# flasher.net
KiCad netlist of a schematic drawn in EAGLE
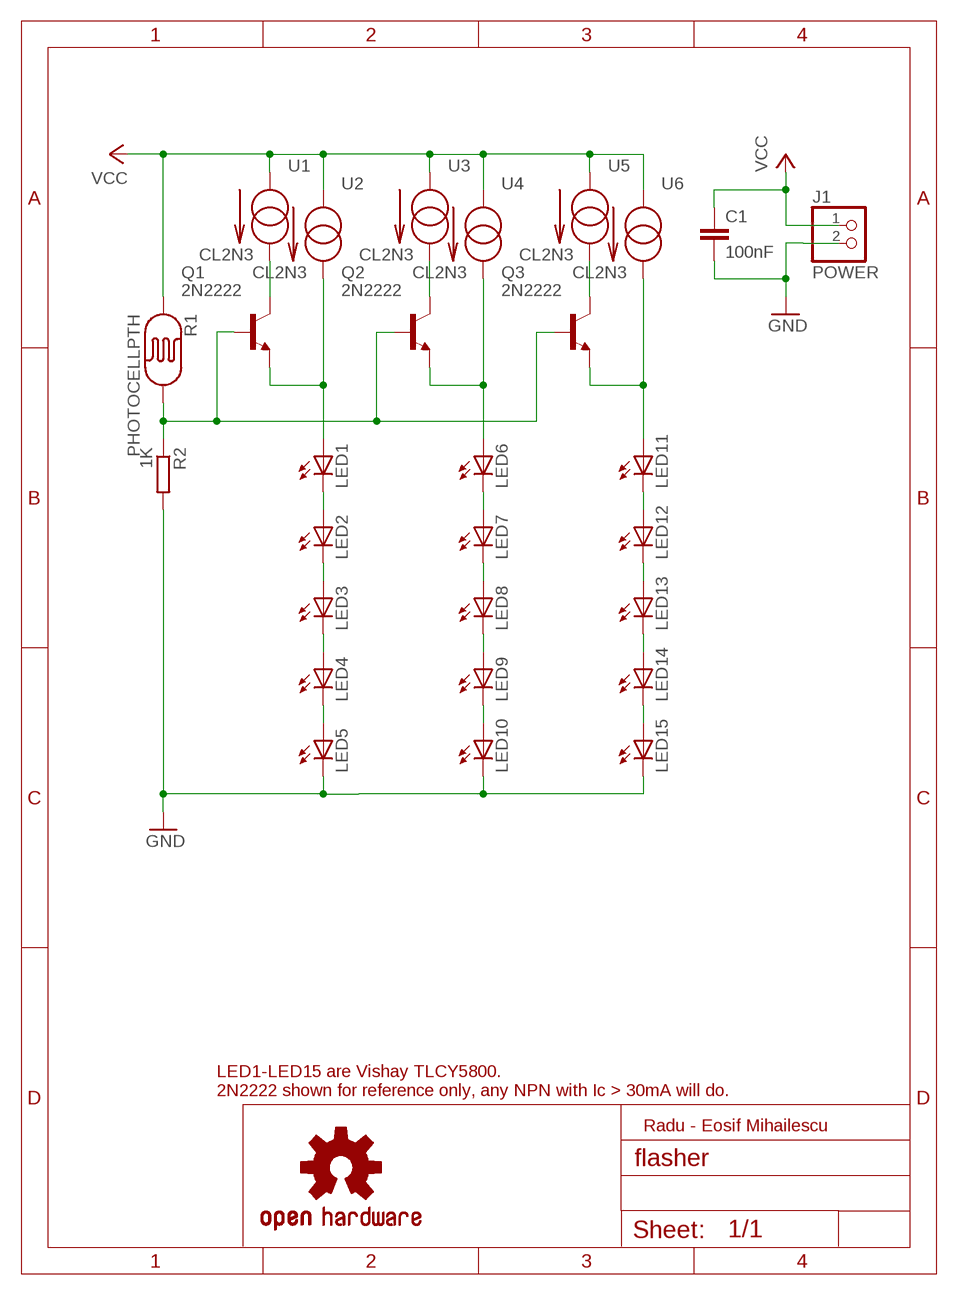
[diagram p0: schematic, sheet 1]

(export (version "E")
  (design (tool "Eeschema 10.0.6"))
  (components
    (comp (ref "C1")
      (value "100nF")
      (footprint "eagle-import:C050-025X075")
      (libsource (lib "eagle-import") (part "C-EU050-025X075"))
    )
    (comp (ref "J1")
      (value "POWER")
      (footprint "eagle-import:1X02_90")
      (libsource (lib "eagle-import") (part "PINHD-1X2/90"))
    )
    (comp (ref "LED1")
      (value "LED5MM")
      (footprint "eagle-import:LED5MM")
      (libsource (lib "eagle-import") (part "LED5MM"))
    )
    (comp (ref "LED2")
      (value "LED5MM")
      (footprint "eagle-import:LED5MM")
      (libsource (lib "eagle-import") (part "LED5MM"))
    )
    (comp (ref "LED3")
      (value "LED5MM")
      (footprint "eagle-import:LED5MM")
      (libsource (lib "eagle-import") (part "LED5MM"))
    )
    (comp (ref "LED4")
      (value "LED5MM")
      (footprint "eagle-import:LED5MM")
      (libsource (lib "eagle-import") (part "LED5MM"))
    )
    (comp (ref "LED5")
      (value "LED5MM")
      (footprint "eagle-import:LED5MM")
      (libsource (lib "eagle-import") (part "LED5MM"))
    )
    (comp (ref "LED6")
      (value "LED5MM")
      (footprint "eagle-import:LED5MM")
      (libsource (lib "eagle-import") (part "LED5MM"))
    )
    (comp (ref "LED7")
      (value "LED5MM")
      (footprint "eagle-import:LED5MM")
      (libsource (lib "eagle-import") (part "LED5MM"))
    )
    (comp (ref "LED8")
      (value "LED5MM")
      (footprint "eagle-import:LED5MM")
      (libsource (lib "eagle-import") (part "LED5MM"))
    )
    (comp (ref "LED9")
      (value "LED5MM")
      (footprint "eagle-import:LED5MM")
      (libsource (lib "eagle-import") (part "LED5MM"))
    )
    (comp (ref "LED10")
      (value "LED5MM")
      (footprint "eagle-import:LED5MM")
      (libsource (lib "eagle-import") (part "LED5MM"))
    )
    (comp (ref "LED11")
      (value "LED5MM")
      (footprint "eagle-import:LED5MM")
      (libsource (lib "eagle-import") (part "LED5MM"))
    )
    (comp (ref "LED12")
      (value "LED5MM")
      (footprint "eagle-import:LED5MM")
      (libsource (lib "eagle-import") (part "LED5MM"))
    )
    (comp (ref "LED13")
      (value "LED5MM")
      (footprint "eagle-import:LED5MM")
      (libsource (lib "eagle-import") (part "LED5MM"))
    )
    (comp (ref "LED14")
      (value "LED5MM")
      (footprint "eagle-import:LED5MM")
      (libsource (lib "eagle-import") (part "LED5MM"))
    )
    (comp (ref "LED15")
      (value "LED5MM")
      (footprint "eagle-import:LED5MM")
      (libsource (lib "eagle-import") (part "LED5MM"))
    )
    (comp (ref "LOGO1")
      (value "OSHW-LOGOL")
      (footprint "eagle-import:OSHW-LOGO-L")
      (libsource (lib "eagle-import") (part "OSHW-LOGOL"))
    )
    (comp (ref "Q1")
      (value "2N2222")
      (footprint "eagle-import:TO92-EBC")
      (libsource (lib "eagle-import") (part "-NPN-TO92-EBC2N2222"))
    )
    (comp (ref "Q2")
      (value "2N2222")
      (footprint "eagle-import:TO92-EBC")
      (libsource (lib "eagle-import") (part "-NPN-TO92-EBC2N2222"))
    )
    (comp (ref "Q3")
      (value "2N2222")
      (footprint "eagle-import:TO92-EBC")
      (libsource (lib "eagle-import") (part "-NPN-TO92-EBC2N2222"))
    )
    (comp (ref "R1")
      (value "PHOTOCELLPTH")
      (footprint "eagle-import:PHOTOCELL")
      (libsource (lib "eagle-import") (part "PHOTOCELLPTH"))
    )
    (comp (ref "R2")
      (value "1K")
      (footprint "eagle-import:0204_7")
      (libsource (lib "eagle-import") (part "R-EU_0204/7"))
    )
    (comp (ref "U1")
      (value "CL2N3")
      (footprint "eagle-import:TO-92")
      (libsource (lib "eagle-import") (part "CL2N3"))
    )
    (comp (ref "U2")
      (value "CL2N3")
      (footprint "eagle-import:TO-92")
      (libsource (lib "eagle-import") (part "CL2N3"))
    )
    (comp (ref "U3")
      (value "CL2N3")
      (footprint "eagle-import:TO-92")
      (libsource (lib "eagle-import") (part "CL2N3"))
    )
    (comp (ref "U4")
      (value "CL2N3")
      (footprint "eagle-import:TO-92")
      (libsource (lib "eagle-import") (part "CL2N3"))
    )
    (comp (ref "U5")
      (value "CL2N3")
      (footprint "eagle-import:TO-92")
      (libsource (lib "eagle-import") (part "CL2N3"))
    )
    (comp (ref "U6")
      (value "CL2N3")
      (footprint "eagle-import:TO-92")
      (libsource (lib "eagle-import") (part "CL2N3"))
    )
  )
  (nets
    (net (code "1") (name "GND") (class "Default")
      (node (ref "C1") (pin "2") (pinfunction "2_2") (pintype "passive"))
      (node (ref "J1") (pin "2") (pinfunction "2_2") (pintype "passive"))
      (node (ref "LED10") (pin "K") (pinfunction "C_K") (pintype "passive"))
      (node (ref "LED15") (pin "K") (pinfunction "C_K") (pintype "passive"))
      (node (ref "LED5") (pin "K") (pinfunction "C_K") (pintype "passive"))
      (node (ref "R2") (pin "2") (pinfunction "2_2") (pintype "passive"))
    )
    (net (code "2") (name "Net-(LED1-C)") (class "Default")
      (node (ref "LED1") (pin "K") (pinfunction "C_K") (pintype "passive"))
      (node (ref "LED2") (pin "A") (pinfunction "A_A") (pintype "passive"))
    )
    (net (code "3") (name "Net-(LED2-C)") (class "Default")
      (node (ref "LED2") (pin "K") (pinfunction "C_K") (pintype "passive"))
      (node (ref "LED3") (pin "A") (pinfunction "A_A") (pintype "passive"))
    )
    (net (code "4") (name "Net-(LED3-C)") (class "Default")
      (node (ref "LED3") (pin "K") (pinfunction "C_K") (pintype "passive"))
      (node (ref "LED4") (pin "A") (pinfunction "A_A") (pintype "passive"))
    )
    (net (code "5") (name "Net-(LED4-C)") (class "Default")
      (node (ref "LED4") (pin "K") (pinfunction "C_K") (pintype "passive"))
      (node (ref "LED5") (pin "A") (pinfunction "A_A") (pintype "passive"))
    )
    (net (code "6") (name "Net-(LED6-C)") (class "Default")
      (node (ref "LED6") (pin "K") (pinfunction "C_K") (pintype "passive"))
      (node (ref "LED7") (pin "A") (pinfunction "A_A") (pintype "passive"))
    )
    (net (code "7") (name "Net-(LED7-C)") (class "Default")
      (node (ref "LED7") (pin "K") (pinfunction "C_K") (pintype "passive"))
      (node (ref "LED8") (pin "A") (pinfunction "A_A") (pintype "passive"))
    )
    (net (code "8") (name "Net-(LED8-C)") (class "Default")
      (node (ref "LED8") (pin "K") (pinfunction "C_K") (pintype "passive"))
      (node (ref "LED9") (pin "A") (pinfunction "A_A") (pintype "passive"))
    )
    (net (code "9") (name "Net-(LED9-C)") (class "Default")
      (node (ref "LED10") (pin "A") (pinfunction "A_A") (pintype "passive"))
      (node (ref "LED9") (pin "K") (pinfunction "C_K") (pintype "passive"))
    )
    (net (code "10") (name "Net-(LED11-C)") (class "Default")
      (node (ref "LED11") (pin "K") (pinfunction "C_K") (pintype "passive"))
      (node (ref "LED12") (pin "A") (pinfunction "A_A") (pintype "passive"))
    )
    (net (code "11") (name "Net-(LED12-C)") (class "Default")
      (node (ref "LED12") (pin "K") (pinfunction "C_K") (pintype "passive"))
      (node (ref "LED13") (pin "A") (pinfunction "A_A") (pintype "passive"))
    )
    (net (code "12") (name "Net-(LED13-C)") (class "Default")
      (node (ref "LED13") (pin "K") (pinfunction "C_K") (pintype "passive"))
      (node (ref "LED14") (pin "A") (pinfunction "A_A") (pintype "passive"))
    )
    (net (code "13") (name "Net-(LED14-C)") (class "Default")
      (node (ref "LED14") (pin "K") (pinfunction "C_K") (pintype "passive"))
      (node (ref "LED15") (pin "A") (pinfunction "A_A") (pintype "passive"))
    )
    (net (code "14") (name "Net-(R1-P$2)") (class "Default")
      (node (ref "Q1") (pin "B") (pinfunction "B_B") (pintype "passive"))
      (node (ref "Q2") (pin "B") (pinfunction "B_B") (pintype "passive"))
      (node (ref "Q3") (pin "B") (pinfunction "B_B") (pintype "passive"))
      (node (ref "R1") (pin "2") (pinfunction "P$2_2") (pintype "bidirectional"))
      (node (ref "R2") (pin "1") (pinfunction "1_1") (pintype "passive"))
    )
    (net (code "15") (name "Net-(U1-OUT)") (class "Default")
      (node (ref "Q1") (pin "C") (pinfunction "C_C") (pintype "passive"))
      (node (ref "U1") (pin "3") (pinfunction "OUT_3") (pintype "output"))
    )
    (net (code "16") (name "Net-(U2-OUT)") (class "Default")
      (node (ref "LED1") (pin "A") (pinfunction "A_A") (pintype "passive"))
      (node (ref "Q1") (pin "E") (pinfunction "E_E") (pintype "passive"))
      (node (ref "U2") (pin "3") (pinfunction "OUT_3") (pintype "output"))
    )
    (net (code "17") (name "Net-(U3-OUT)") (class "Default")
      (node (ref "Q2") (pin "C") (pinfunction "C_C") (pintype "passive"))
      (node (ref "U3") (pin "3") (pinfunction "OUT_3") (pintype "output"))
    )
    (net (code "18") (name "Net-(U4-OUT)") (class "Default")
      (node (ref "LED6") (pin "A") (pinfunction "A_A") (pintype "passive"))
      (node (ref "Q2") (pin "E") (pinfunction "E_E") (pintype "passive"))
      (node (ref "U4") (pin "3") (pinfunction "OUT_3") (pintype "output"))
    )
    (net (code "19") (name "Net-(U5-OUT)") (class "Default")
      (node (ref "Q3") (pin "C") (pinfunction "C_C") (pintype "passive"))
      (node (ref "U5") (pin "3") (pinfunction "OUT_3") (pintype "output"))
    )
    (net (code "20") (name "Net-(U6-OUT)") (class "Default")
      (node (ref "LED11") (pin "A") (pinfunction "A_A") (pintype "passive"))
      (node (ref "Q3") (pin "E") (pinfunction "E_E") (pintype "passive"))
      (node (ref "U6") (pin "3") (pinfunction "OUT_3") (pintype "output"))
    )
    (net (code "21") (name "VCC") (class "Default")
      (node (ref "C1") (pin "1") (pinfunction "1_1") (pintype "passive"))
      (node (ref "J1") (pin "1") (pinfunction "1_1") (pintype "passive"))
      (node (ref "R1") (pin "1") (pinfunction "P$1_1") (pintype "bidirectional"))
      (node (ref "U1") (pin "1") (pinfunction "IN_1") (pintype "input"))
      (node (ref "U2") (pin "1") (pinfunction "IN_1") (pintype "input"))
      (node (ref "U3") (pin "1") (pinfunction "IN_1") (pintype "input"))
      (node (ref "U4") (pin "1") (pinfunction "IN_1") (pintype "input"))
      (node (ref "U5") (pin "1") (pinfunction "IN_1") (pintype "input"))
      (node (ref "U6") (pin "1") (pinfunction "IN_1") (pintype "input"))
    )
  )
)
